# Motor_Drivers.net
KiCad netlist of a schematic drawn in Altium Designer
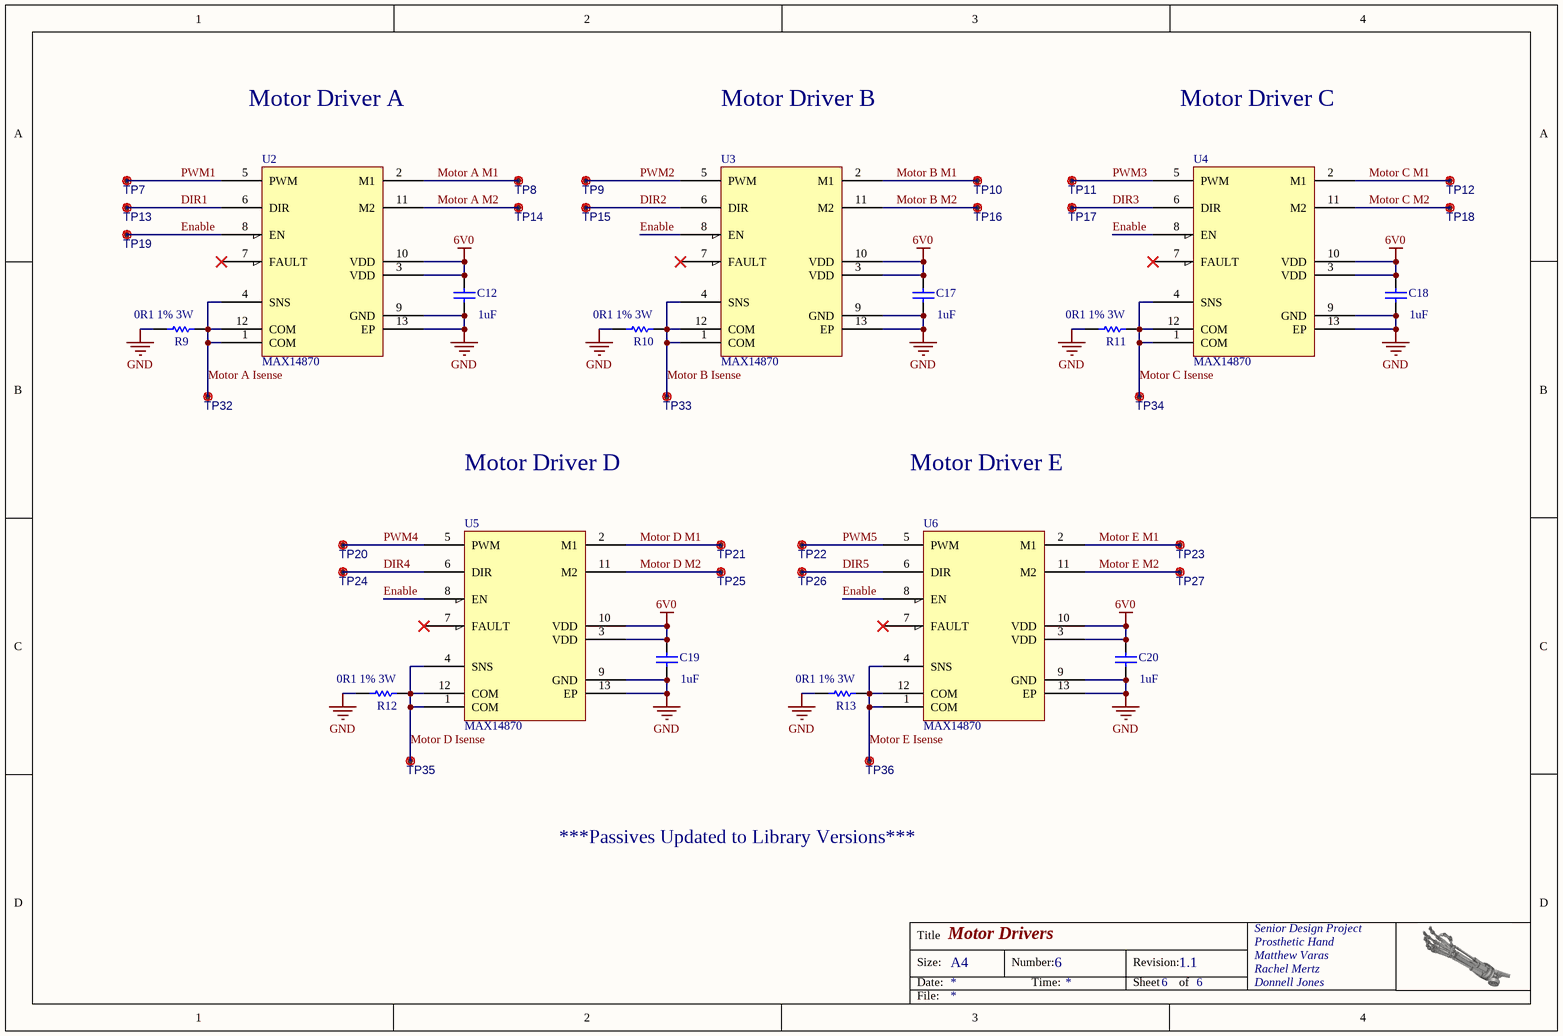
[diagram p0: Motor_Drivers.SchDoc]

(export (version "E")
  (design (tool "Eeschema 10.0.6"))
  (components
    (comp (ref "C12")
      (value "1uF")
      (footprint "0402 Cap")
      (description "1µF ±10% 16V X5R Ceramic Capacitor 0402")
      (fields (field (name "Comment") "Cap"))
      (libsource (lib "Prosthetic Hand Schematic Lib") (part "Cap 0402"))
    )
    (comp (ref "C17")
      (value "1uF")
      (footprint "0402 Cap")
      (description "1µF ±10% 16V X5R Ceramic Capacitor 0402")
      (fields (field (name "Comment") "Cap"))
      (libsource (lib "Prosthetic Hand Schematic Lib") (part "Cap 0402"))
    )
    (comp (ref "C18")
      (value "1uF")
      (footprint "0402 Cap")
      (description "1µF ±10% 16V X5R Ceramic Capacitor 0402")
      (fields (field (name "Comment") "Cap"))
      (libsource (lib "Prosthetic Hand Schematic Lib") (part "Cap 0402"))
    )
    (comp (ref "C19")
      (value "1uF")
      (footprint "0402 Cap")
      (description "1µF ±10% 16V X5R Ceramic Capacitor 0402")
      (fields (field (name "Comment") "Cap"))
      (libsource (lib "Prosthetic Hand Schematic Lib") (part "Cap 0402"))
    )
    (comp (ref "C20")
      (value "1uF")
      (footprint "0402 Cap")
      (description "1µF ±10% 16V X5R Ceramic Capacitor 0402")
      (fields (field (name "Comment") "Cap"))
      (libsource (lib "Prosthetic Hand Schematic Lib") (part "Cap 0402"))
    )
    (comp (ref "R9")
      (value "0R1 1% 3W")
      (footprint "2512 Resistor")
      (description "RES SMD 0.1 OHM 1% 3W 2512")
      (libsource (lib "Prosthetic Hand Schematic Lib") (part "Resistor 2512"))
    )
    (comp (ref "R10")
      (value "0R1 1% 3W")
      (footprint "2512 Resistor")
      (description "RES SMD 0.1 OHM 1% 3W 2512")
      (libsource (lib "Prosthetic Hand Schematic Lib") (part "Resistor 2512"))
    )
    (comp (ref "R11")
      (value "0R1 1% 3W")
      (footprint "2512 Resistor")
      (description "RES SMD 0.1 OHM 1% 3W 2512")
      (libsource (lib "Prosthetic Hand Schematic Lib") (part "Resistor 2512"))
    )
    (comp (ref "R12")
      (value "0R1 1% 3W")
      (footprint "2512 Resistor")
      (description "RES SMD 0.1 OHM 1% 3W 2512")
      (libsource (lib "Prosthetic Hand Schematic Lib") (part "Resistor 2512"))
    )
    (comp (ref "R13")
      (value "0R1 1% 3W")
      (footprint "2512 Resistor")
      (description "RES SMD 0.1 OHM 1% 3W 2512")
      (libsource (lib "Prosthetic Hand Schematic Lib") (part "Resistor 2512"))
    )
    (comp (ref "TP7")
      (value "Test Point")
      (footprint "Testpoint_70")
      (description "Test Pad")
      (libsource (lib "Prosthetic Hand Schematic Lib") (part "Test Point"))
    )
    (comp (ref "TP8")
      (value "Test Point")
      (footprint "Testpoint_70")
      (description "Test Pad")
      (libsource (lib "Prosthetic Hand Schematic Lib") (part "Test Point"))
    )
    (comp (ref "TP9")
      (value "Test Point")
      (footprint "Testpoint_70")
      (description "Test Pad")
      (libsource (lib "Prosthetic Hand Schematic Lib") (part "Test Point"))
    )
    (comp (ref "TP10")
      (value "Test Point")
      (footprint "Testpoint_70")
      (description "Test Pad")
      (libsource (lib "Prosthetic Hand Schematic Lib") (part "Test Point"))
    )
    (comp (ref "TP11")
      (value "Test Point")
      (footprint "Testpoint_70")
      (description "Test Pad")
      (libsource (lib "Prosthetic Hand Schematic Lib") (part "Test Point"))
    )
    (comp (ref "TP12")
      (value "Test Point")
      (footprint "Testpoint_70")
      (description "Test Pad")
      (libsource (lib "Prosthetic Hand Schematic Lib") (part "Test Point"))
    )
    (comp (ref "TP13")
      (value "Test Point")
      (footprint "Testpoint_70")
      (description "Test Pad")
      (libsource (lib "Prosthetic Hand Schematic Lib") (part "Test Point"))
    )
    (comp (ref "TP14")
      (value "Test Point")
      (footprint "Testpoint_70")
      (description "Test Pad")
      (libsource (lib "Prosthetic Hand Schematic Lib") (part "Test Point"))
    )
    (comp (ref "TP15")
      (value "Test Point")
      (footprint "Testpoint_70")
      (description "Test Pad")
      (libsource (lib "Prosthetic Hand Schematic Lib") (part "Test Point"))
    )
    (comp (ref "TP16")
      (value "Test Point")
      (footprint "Testpoint_70")
      (description "Test Pad")
      (libsource (lib "Prosthetic Hand Schematic Lib") (part "Test Point"))
    )
    (comp (ref "TP17")
      (value "Test Point")
      (footprint "Testpoint_70")
      (description "Test Pad")
      (libsource (lib "Prosthetic Hand Schematic Lib") (part "Test Point"))
    )
    (comp (ref "TP18")
      (value "Test Point")
      (footprint "Testpoint_70")
      (description "Test Pad")
      (libsource (lib "Prosthetic Hand Schematic Lib") (part "Test Point"))
    )
    (comp (ref "TP19")
      (value "Test Point")
      (footprint "Testpoint_70")
      (description "Test Pad")
      (libsource (lib "Prosthetic Hand Schematic Lib") (part "Test Point"))
    )
    (comp (ref "TP20")
      (value "Test Point")
      (footprint "Testpoint_70")
      (description "Test Pad")
      (libsource (lib "Prosthetic Hand Schematic Lib") (part "Test Point"))
    )
    (comp (ref "TP21")
      (value "Test Point")
      (footprint "Testpoint_70")
      (description "Test Pad")
      (libsource (lib "Prosthetic Hand Schematic Lib") (part "Test Point"))
    )
    (comp (ref "TP22")
      (value "Test Point")
      (footprint "Testpoint_70")
      (description "Test Pad")
      (libsource (lib "Prosthetic Hand Schematic Lib") (part "Test Point"))
    )
    (comp (ref "TP23")
      (value "Test Point")
      (footprint "Testpoint_70")
      (description "Test Pad")
      (libsource (lib "Prosthetic Hand Schematic Lib") (part "Test Point"))
    )
    (comp (ref "TP24")
      (value "Test Point")
      (footprint "Testpoint_70")
      (description "Test Pad")
      (libsource (lib "Prosthetic Hand Schematic Lib") (part "Test Point"))
    )
    (comp (ref "TP25")
      (value "Test Point")
      (footprint "Testpoint_70")
      (description "Test Pad")
      (libsource (lib "Prosthetic Hand Schematic Lib") (part "Test Point"))
    )
    (comp (ref "TP26")
      (value "Test Point")
      (footprint "Testpoint_70")
      (description "Test Pad")
      (libsource (lib "Prosthetic Hand Schematic Lib") (part "Test Point"))
    )
    (comp (ref "TP27")
      (value "Test Point")
      (footprint "Testpoint_70")
      (description "Test Pad")
      (libsource (lib "Prosthetic Hand Schematic Lib") (part "Test Point"))
    )
    (comp (ref "TP32")
      (value "Test Point")
      (footprint "Testpoint_70")
      (description "Test Pad")
      (libsource (lib "Prosthetic Hand Schematic Lib") (part "Test Point"))
    )
    (comp (ref "TP33")
      (value "Test Point")
      (footprint "Testpoint_70")
      (description "Test Pad")
      (libsource (lib "Prosthetic Hand Schematic Lib") (part "Test Point"))
    )
    (comp (ref "TP34")
      (value "Test Point")
      (footprint "Testpoint_70")
      (description "Test Pad")
      (libsource (lib "Prosthetic Hand Schematic Lib") (part "Test Point"))
    )
    (comp (ref "TP35")
      (value "Test Point")
      (footprint "Testpoint_70")
      (description "Test Pad")
      (libsource (lib "Prosthetic Hand Schematic Lib") (part "Test Point"))
    )
    (comp (ref "TP36")
      (value "Test Point")
      (footprint "Testpoint_70")
      (description "Test Pad")
      (libsource (lib "Prosthetic Hand Schematic Lib") (part "Test Point"))
    )
    (comp (ref "U2")
      (value "MAX14870")
      (footprint "12L TDFN 3x3")
      (description "IC MOTOR DVR DC FULL BR 12TDFN")
      (libsource (lib "Prosthetic Hand Schematic Lib") (part "MAX14870"))
    )
    (comp (ref "U3")
      (value "MAX14870")
      (footprint "12L TDFN 3x3")
      (description "IC MOTOR DVR DC FULL BR 12TDFN")
      (libsource (lib "Prosthetic Hand Schematic Lib") (part "MAX14870"))
    )
    (comp (ref "U4")
      (value "MAX14870")
      (footprint "12L TDFN 3x3")
      (description "IC MOTOR DVR DC FULL BR 12TDFN")
      (libsource (lib "Prosthetic Hand Schematic Lib") (part "MAX14870"))
    )
    (comp (ref "U5")
      (value "MAX14870")
      (footprint "12L TDFN 3x3")
      (description "IC MOTOR DVR DC FULL BR 12TDFN")
      (libsource (lib "Prosthetic Hand Schematic Lib") (part "MAX14870"))
    )
    (comp (ref "U6")
      (value "MAX14870")
      (footprint "12L TDFN 3x3")
      (description "IC MOTOR DVR DC FULL BR 12TDFN")
      (libsource (lib "Prosthetic Hand Schematic Lib") (part "MAX14870"))
    )
  )
  (nets
    (net (code "1") (name "/DIR1") (class "Default")
      (node (ref "TP13") (pin "1") (pinfunction "M80_1") (pintype "passive"))
      (node (ref "U2") (pin "6") (pinfunction "DIR_6") (pintype "passive"))
    )
    (net (code "2") (name "/DIR2") (class "Default")
      (node (ref "TP15") (pin "1") (pinfunction "M80_1") (pintype "passive"))
      (node (ref "U3") (pin "6") (pinfunction "DIR_6") (pintype "passive"))
    )
    (net (code "3") (name "/DIR3") (class "Default")
      (node (ref "TP17") (pin "1") (pinfunction "M80_1") (pintype "passive"))
      (node (ref "U4") (pin "6") (pinfunction "DIR_6") (pintype "passive"))
    )
    (net (code "4") (name "/DIR4") (class "Default")
      (node (ref "TP24") (pin "1") (pinfunction "M80_1") (pintype "passive"))
      (node (ref "U5") (pin "6") (pinfunction "DIR_6") (pintype "passive"))
    )
    (net (code "5") (name "/DIR5") (class "Default")
      (node (ref "TP26") (pin "1") (pinfunction "M80_1") (pintype "passive"))
      (node (ref "U6") (pin "6") (pinfunction "DIR_6") (pintype "passive"))
    )
    (net (code "6") (name "/Enable") (class "Default")
      (node (ref "TP19") (pin "1") (pinfunction "M80_1") (pintype "passive"))
      (node (ref "U2") (pin "8") (pinfunction "EN_8") (pintype "passive"))
      (node (ref "U3") (pin "8") (pinfunction "EN_8") (pintype "passive"))
      (node (ref "U4") (pin "8") (pinfunction "EN_8") (pintype "passive"))
      (node (ref "U5") (pin "8") (pinfunction "EN_8") (pintype "passive"))
      (node (ref "U6") (pin "8") (pinfunction "EN_8") (pintype "passive"))
    )
    (net (code "7") (name "/Motor A Isense") (class "Default")
      (node (ref "R9") (pin "2") (pinfunction "2_2") (pintype "passive"))
      (node (ref "TP32") (pin "1") (pinfunction "M80_1") (pintype "passive"))
      (node (ref "U2") (pin "1") (pinfunction "COM_1") (pintype "passive"))
      (node (ref "U2") (pin "12") (pinfunction "COM_12") (pintype "passive"))
      (node (ref "U2") (pin "4") (pinfunction "SNS_4") (pintype "passive"))
    )
    (net (code "8") (name "/Motor A M1") (class "Default")
      (node (ref "TP8") (pin "1") (pinfunction "M80_1") (pintype "passive"))
      (node (ref "U2") (pin "2") (pinfunction "M1_2") (pintype "passive"))
    )
    (net (code "9") (name "/Motor A M2") (class "Default")
      (node (ref "TP14") (pin "1") (pinfunction "M80_1") (pintype "passive"))
      (node (ref "U2") (pin "11") (pinfunction "M2_11") (pintype "passive"))
    )
    (net (code "10") (name "/Motor B Isense") (class "Default")
      (node (ref "R10") (pin "2") (pinfunction "2_2") (pintype "passive"))
      (node (ref "TP33") (pin "1") (pinfunction "M80_1") (pintype "passive"))
      (node (ref "U3") (pin "1") (pinfunction "COM_1") (pintype "passive"))
      (node (ref "U3") (pin "12") (pinfunction "COM_12") (pintype "passive"))
      (node (ref "U3") (pin "4") (pinfunction "SNS_4") (pintype "passive"))
    )
    (net (code "11") (name "/Motor B M1") (class "Default")
      (node (ref "TP10") (pin "1") (pinfunction "M80_1") (pintype "passive"))
      (node (ref "U3") (pin "2") (pinfunction "M1_2") (pintype "passive"))
    )
    (net (code "12") (name "/Motor B M2") (class "Default")
      (node (ref "TP16") (pin "1") (pinfunction "M80_1") (pintype "passive"))
      (node (ref "U3") (pin "11") (pinfunction "M2_11") (pintype "passive"))
    )
    (net (code "13") (name "/Motor C Isense") (class "Default")
      (node (ref "R11") (pin "2") (pinfunction "2_2") (pintype "passive"))
      (node (ref "TP34") (pin "1") (pinfunction "M80_1") (pintype "passive"))
      (node (ref "U4") (pin "1") (pinfunction "COM_1") (pintype "passive"))
      (node (ref "U4") (pin "12") (pinfunction "COM_12") (pintype "passive"))
      (node (ref "U4") (pin "4") (pinfunction "SNS_4") (pintype "passive"))
    )
    (net (code "14") (name "/Motor C M1") (class "Default")
      (node (ref "TP12") (pin "1") (pinfunction "M80_1") (pintype "passive"))
      (node (ref "U4") (pin "2") (pinfunction "M1_2") (pintype "passive"))
    )
    (net (code "15") (name "/Motor C M2") (class "Default")
      (node (ref "TP18") (pin "1") (pinfunction "M80_1") (pintype "passive"))
      (node (ref "U4") (pin "11") (pinfunction "M2_11") (pintype "passive"))
    )
    (net (code "16") (name "/Motor D Isense") (class "Default")
      (node (ref "R12") (pin "2") (pinfunction "2_2") (pintype "passive"))
      (node (ref "TP35") (pin "1") (pinfunction "M80_1") (pintype "passive"))
      (node (ref "U5") (pin "1") (pinfunction "COM_1") (pintype "passive"))
      (node (ref "U5") (pin "12") (pinfunction "COM_12") (pintype "passive"))
      (node (ref "U5") (pin "4") (pinfunction "SNS_4") (pintype "passive"))
    )
    (net (code "17") (name "/Motor D M1") (class "Default")
      (node (ref "TP21") (pin "1") (pinfunction "M80_1") (pintype "passive"))
      (node (ref "U5") (pin "2") (pinfunction "M1_2") (pintype "passive"))
    )
    (net (code "18") (name "/Motor D M2") (class "Default")
      (node (ref "TP25") (pin "1") (pinfunction "M80_1") (pintype "passive"))
      (node (ref "U5") (pin "11") (pinfunction "M2_11") (pintype "passive"))
    )
    (net (code "19") (name "/Motor E Isense") (class "Default")
      (node (ref "R13") (pin "2") (pinfunction "2_2") (pintype "passive"))
      (node (ref "TP36") (pin "1") (pinfunction "M80_1") (pintype "passive"))
      (node (ref "U6") (pin "1") (pinfunction "COM_1") (pintype "passive"))
      (node (ref "U6") (pin "12") (pinfunction "COM_12") (pintype "passive"))
      (node (ref "U6") (pin "4") (pinfunction "SNS_4") (pintype "passive"))
    )
    (net (code "20") (name "/Motor E M1") (class "Default")
      (node (ref "TP23") (pin "1") (pinfunction "M80_1") (pintype "passive"))
      (node (ref "U6") (pin "2") (pinfunction "M1_2") (pintype "passive"))
    )
    (net (code "21") (name "/Motor E M2") (class "Default")
      (node (ref "TP27") (pin "1") (pinfunction "M80_1") (pintype "passive"))
      (node (ref "U6") (pin "11") (pinfunction "M2_11") (pintype "passive"))
    )
    (net (code "22") (name "/PWM1") (class "Default")
      (node (ref "TP7") (pin "1") (pinfunction "M80_1") (pintype "passive"))
      (node (ref "U2") (pin "5") (pinfunction "PWM_5") (pintype "passive"))
    )
    (net (code "23") (name "/PWM2") (class "Default")
      (node (ref "TP9") (pin "1") (pinfunction "M80_1") (pintype "passive"))
      (node (ref "U3") (pin "5") (pinfunction "PWM_5") (pintype "passive"))
    )
    (net (code "24") (name "/PWM3") (class "Default")
      (node (ref "TP11") (pin "1") (pinfunction "M80_1") (pintype "passive"))
      (node (ref "U4") (pin "5") (pinfunction "PWM_5") (pintype "passive"))
    )
    (net (code "25") (name "/PWM4") (class "Default")
      (node (ref "TP20") (pin "1") (pinfunction "M80_1") (pintype "passive"))
      (node (ref "U5") (pin "5") (pinfunction "PWM_5") (pintype "passive"))
    )
    (net (code "26") (name "/PWM5") (class "Default")
      (node (ref "TP22") (pin "1") (pinfunction "M80_1") (pintype "passive"))
      (node (ref "U6") (pin "5") (pinfunction "PWM_5") (pintype "passive"))
    )
    (net (code "27") (name "6V0") (class "Default")
      (node (ref "C12") (pin "2") (pinfunction "2_2") (pintype "passive"))
      (node (ref "C17") (pin "2") (pinfunction "2_2") (pintype "passive"))
      (node (ref "C18") (pin "2") (pinfunction "2_2") (pintype "passive"))
      (node (ref "C19") (pin "2") (pinfunction "2_2") (pintype "passive"))
      (node (ref "C20") (pin "2") (pinfunction "2_2") (pintype "passive"))
      (node (ref "U2") (pin "10") (pinfunction "VDD_10") (pintype "passive"))
      (node (ref "U2") (pin "3") (pinfunction "VDD_3") (pintype "passive"))
      (node (ref "U3") (pin "10") (pinfunction "VDD_10") (pintype "passive"))
      (node (ref "U3") (pin "3") (pinfunction "VDD_3") (pintype "passive"))
      (node (ref "U4") (pin "10") (pinfunction "VDD_10") (pintype "passive"))
      (node (ref "U4") (pin "3") (pinfunction "VDD_3") (pintype "passive"))
      (node (ref "U5") (pin "10") (pinfunction "VDD_10") (pintype "passive"))
      (node (ref "U5") (pin "3") (pinfunction "VDD_3") (pintype "passive"))
      (node (ref "U6") (pin "10") (pinfunction "VDD_10") (pintype "passive"))
      (node (ref "U6") (pin "3") (pinfunction "VDD_3") (pintype "passive"))
    )
    (net (code "28") (name "GND") (class "Default")
      (node (ref "C12") (pin "1") (pinfunction "1_1") (pintype "passive"))
      (node (ref "C17") (pin "1") (pinfunction "1_1") (pintype "passive"))
      (node (ref "C18") (pin "1") (pinfunction "1_1") (pintype "passive"))
      (node (ref "C19") (pin "1") (pinfunction "1_1") (pintype "passive"))
      (node (ref "C20") (pin "1") (pinfunction "1_1") (pintype "passive"))
      (node (ref "R10") (pin "1") (pinfunction "1_1") (pintype "passive"))
      (node (ref "R11") (pin "1") (pinfunction "1_1") (pintype "passive"))
      (node (ref "R12") (pin "1") (pinfunction "1_1") (pintype "passive"))
      (node (ref "R13") (pin "1") (pinfunction "1_1") (pintype "passive"))
      (node (ref "R9") (pin "1") (pinfunction "1_1") (pintype "passive"))
      (node (ref "U2") (pin "13") (pinfunction "EP_13") (pintype "passive"))
      (node (ref "U2") (pin "9") (pinfunction "GND_9") (pintype "passive"))
      (node (ref "U3") (pin "13") (pinfunction "EP_13") (pintype "passive"))
      (node (ref "U3") (pin "9") (pinfunction "GND_9") (pintype "passive"))
      (node (ref "U4") (pin "13") (pinfunction "EP_13") (pintype "passive"))
      (node (ref "U4") (pin "9") (pinfunction "GND_9") (pintype "passive"))
      (node (ref "U5") (pin "13") (pinfunction "EP_13") (pintype "passive"))
      (node (ref "U5") (pin "9") (pinfunction "GND_9") (pintype "passive"))
      (node (ref "U6") (pin "13") (pinfunction "EP_13") (pintype "passive"))
      (node (ref "U6") (pin "9") (pinfunction "GND_9") (pintype "passive"))
    )
    (net (code "29") (name "unconnected-(U2-FAULT-Pad7)") (class "Default")
      (node (ref "U2") (pin "7") (pinfunction "FAULT_7") (pintype "passive+no_connect"))
    )
    (net (code "30") (name "unconnected-(U3-FAULT-Pad7)") (class "Default")
      (node (ref "U3") (pin "7") (pinfunction "FAULT_7") (pintype "passive+no_connect"))
    )
    (net (code "31") (name "unconnected-(U4-FAULT-Pad7)") (class "Default")
      (node (ref "U4") (pin "7") (pinfunction "FAULT_7") (pintype "passive+no_connect"))
    )
    (net (code "32") (name "unconnected-(U5-FAULT-Pad7)") (class "Default")
      (node (ref "U5") (pin "7") (pinfunction "FAULT_7") (pintype "passive+no_connect"))
    )
    (net (code "33") (name "unconnected-(U6-FAULT-Pad7)") (class "Default")
      (node (ref "U6") (pin "7") (pinfunction "FAULT_7") (pintype "passive+no_connect"))
    )
  )
)
